# WindStation.net
KiCad netlist of a schematic drawn in EAGLE
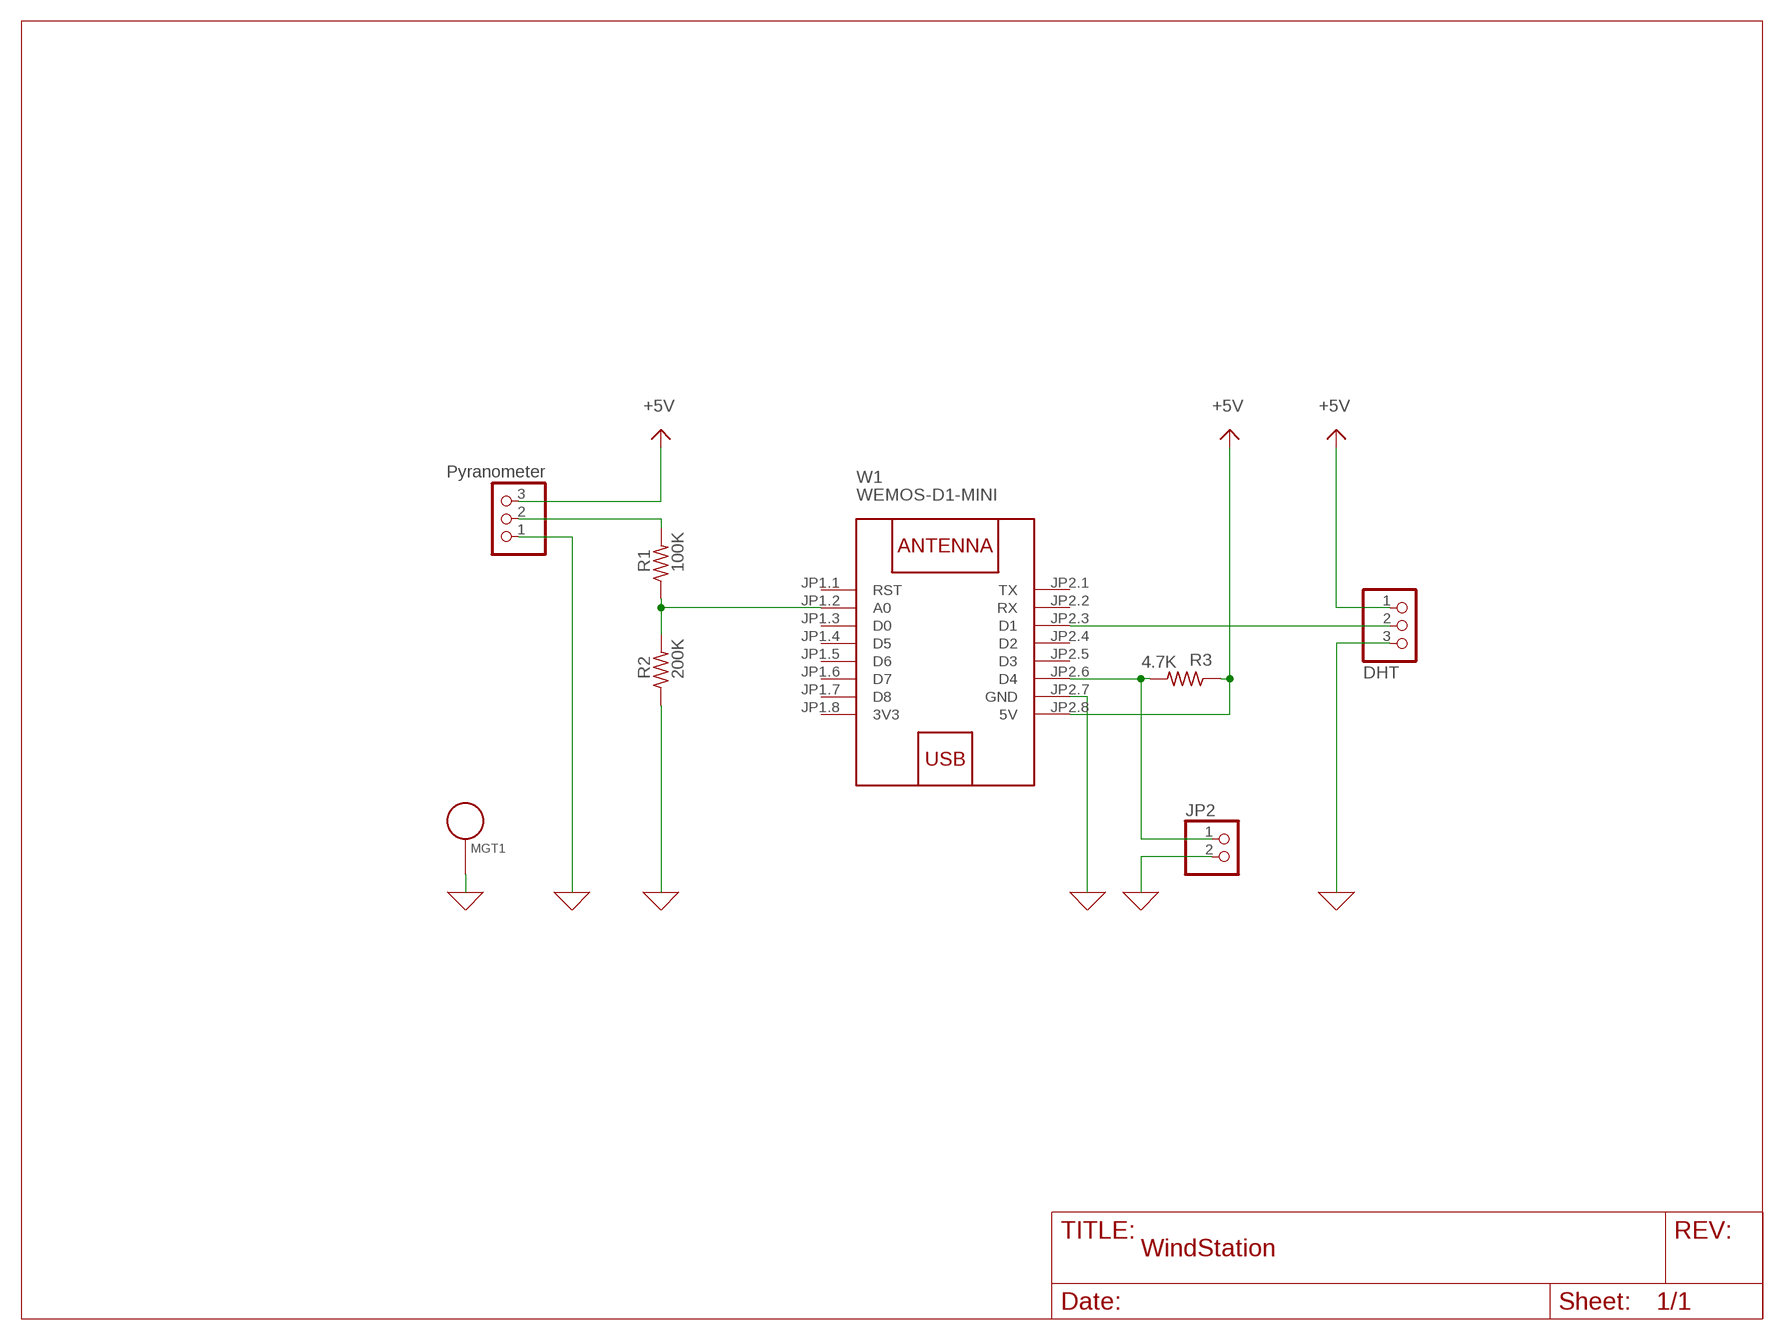
[diagram p0: schematic, sheet 1]

(export (version "E")
  (design (tool "Eeschema 10.0.6"))
  (components
    (comp (ref "JP1")
      (value "Pyranometer")
      (footprint "eagle-import:1X03")
      (libsource (lib "eagle-import") (part "PINHD-1X3"))
    )
    (comp (ref "JP2")
      (value "PINHD-1X2")
      (footprint "eagle-import:1X02")
      (libsource (lib "eagle-import") (part "PINHD-1X2"))
    )
    (comp (ref "JP3")
      (value "DHT")
      (footprint "eagle-import:1X03")
      (libsource (lib "eagle-import") (part "PINHD-1X3"))
    )
    (comp (ref "MGT1")
      (value "BEAGLEBONEBLACK_MOUNTING_HOLE")
      (footprint "eagle-import:BEAGLEBONEBLACK_MOUNTING_HOLE")
      (libsource (lib "eagle-import") (part "BEAGLEBONEBLACK_MOUNTING_HOLE"))
    )
    (comp (ref "R1")
      (value "100K")
      (footprint "eagle-import:0207_10")
      (libsource (lib "eagle-import") (part "R-US_0207/10"))
    )
    (comp (ref "R2")
      (value "200K")
      (footprint "eagle-import:0207_10")
      (libsource (lib "eagle-import") (part "R-US_0207/10"))
    )
    (comp (ref "R3")
      (value "4.7K")
      (footprint "eagle-import:0207_10")
      (libsource (lib "eagle-import") (part "R-US_0207/10"))
    )
    (comp (ref "W1")
      (value "WEMOS-D1-MINI")
      (footprint "eagle-import:WEMOS-D1-MINI")
      (libsource (lib "eagle-import") (part "WEMOS-D1-MINI"))
    )
  )
  (nets
    (net (code "1") (name "/3V3") (class "Default")
      (node (ref "W1") (pin "JP1.8") (pinfunction "3V3_JP1.8") (pintype "power_in"))
    )
    (net (code "2") (name "GND") (class "Default")
      (node (ref "JP1") (pin "1") (pinfunction "1_1") (pintype "passive"))
      (node (ref "JP2") (pin "2") (pinfunction "2_2") (pintype "passive"))
      (node (ref "JP3") (pin "3") (pinfunction "3_3") (pintype "passive"))
      (node (ref "MGT1") (pin "P$1") (pinfunction "P$1_P$1") (pintype "bidirectional"))
      (node (ref "R2") (pin "1") (pinfunction "1_1") (pintype "passive"))
      (node (ref "W1") (pin "JP2.7") (pinfunction "GND_JP2.7") (pintype "power_in"))
    )
    (net (code "3") (name "Net-(JP1-Pad2)") (class "Default")
      (node (ref "JP1") (pin "2") (pinfunction "2_2") (pintype "passive"))
      (node (ref "R1") (pin "2") (pinfunction "2_2") (pintype "passive"))
    )
    (net (code "4") (name "Net-(W1-A0)") (class "Default")
      (node (ref "R1") (pin "1") (pinfunction "1_1") (pintype "passive"))
      (node (ref "R2") (pin "2") (pinfunction "2_2") (pintype "passive"))
      (node (ref "W1") (pin "JP1.2") (pinfunction "A0_JP1.2") (pintype "bidirectional"))
    )
    (net (code "5") (name "Net-(W1-D1)") (class "Default")
      (node (ref "JP3") (pin "2") (pinfunction "2_2") (pintype "passive"))
      (node (ref "W1") (pin "JP2.3") (pinfunction "D1_JP2.3") (pintype "bidirectional"))
    )
    (net (code "6") (name "Net-(W1-D4)") (class "Default")
      (node (ref "JP2") (pin "1") (pinfunction "1_1") (pintype "passive"))
      (node (ref "R3") (pin "2") (pinfunction "2_2") (pintype "passive"))
      (node (ref "W1") (pin "JP2.6") (pinfunction "D4_JP2.6") (pintype "bidirectional"))
    )
    (net (code "7") (name "VCC") (class "Default")
      (node (ref "JP1") (pin "3") (pinfunction "3_3") (pintype "passive"))
      (node (ref "JP3") (pin "1") (pinfunction "1_1") (pintype "passive"))
      (node (ref "R3") (pin "1") (pinfunction "1_1") (pintype "passive"))
      (node (ref "W1") (pin "JP2.8") (pinfunction "5V_JP2.8") (pintype "power_in"))
    )
    (net (code "8") (name "unconnected-(W1-D0-PadJP1.3)") (class "Default")
      (node (ref "W1") (pin "JP1.3") (pinfunction "D0_JP1.3") (pintype "bidirectional"))
    )
    (net (code "9") (name "unconnected-(W1-D2-PadJP2.4)") (class "Default")
      (node (ref "W1") (pin "JP2.4") (pinfunction "D2_JP2.4") (pintype "bidirectional"))
    )
    (net (code "10") (name "unconnected-(W1-D3-PadJP2.5)") (class "Default")
      (node (ref "W1") (pin "JP2.5") (pinfunction "D3_JP2.5") (pintype "bidirectional"))
    )
    (net (code "11") (name "unconnected-(W1-D5-PadJP1.4)") (class "Default")
      (node (ref "W1") (pin "JP1.4") (pinfunction "D5_JP1.4") (pintype "bidirectional"))
    )
    (net (code "12") (name "unconnected-(W1-D6-PadJP1.5)") (class "Default")
      (node (ref "W1") (pin "JP1.5") (pinfunction "D6_JP1.5") (pintype "bidirectional"))
    )
    (net (code "13") (name "unconnected-(W1-D7-PadJP1.6)") (class "Default")
      (node (ref "W1") (pin "JP1.6") (pinfunction "D7_JP1.6") (pintype "bidirectional"))
    )
    (net (code "14") (name "unconnected-(W1-D8-PadJP1.7)") (class "Default")
      (node (ref "W1") (pin "JP1.7") (pinfunction "D8_JP1.7") (pintype "bidirectional"))
    )
    (net (code "15") (name "unconnected-(W1-RST-PadJP1.1)") (class "Default")
      (node (ref "W1") (pin "JP1.1") (pinfunction "RST_JP1.1") (pintype "bidirectional"))
    )
    (net (code "16") (name "unconnected-(W1-RX-PadJP2.2)") (class "Default")
      (node (ref "W1") (pin "JP2.2") (pinfunction "RX_JP2.2") (pintype "bidirectional"))
    )
    (net (code "17") (name "unconnected-(W1-TX-PadJP2.1)") (class "Default")
      (node (ref "W1") (pin "JP2.1") (pinfunction "TX_JP2.1") (pintype "bidirectional"))
    )
  )
)
